# 1_top.net
KiCad netlist of a schematic drawn in Altium Designer
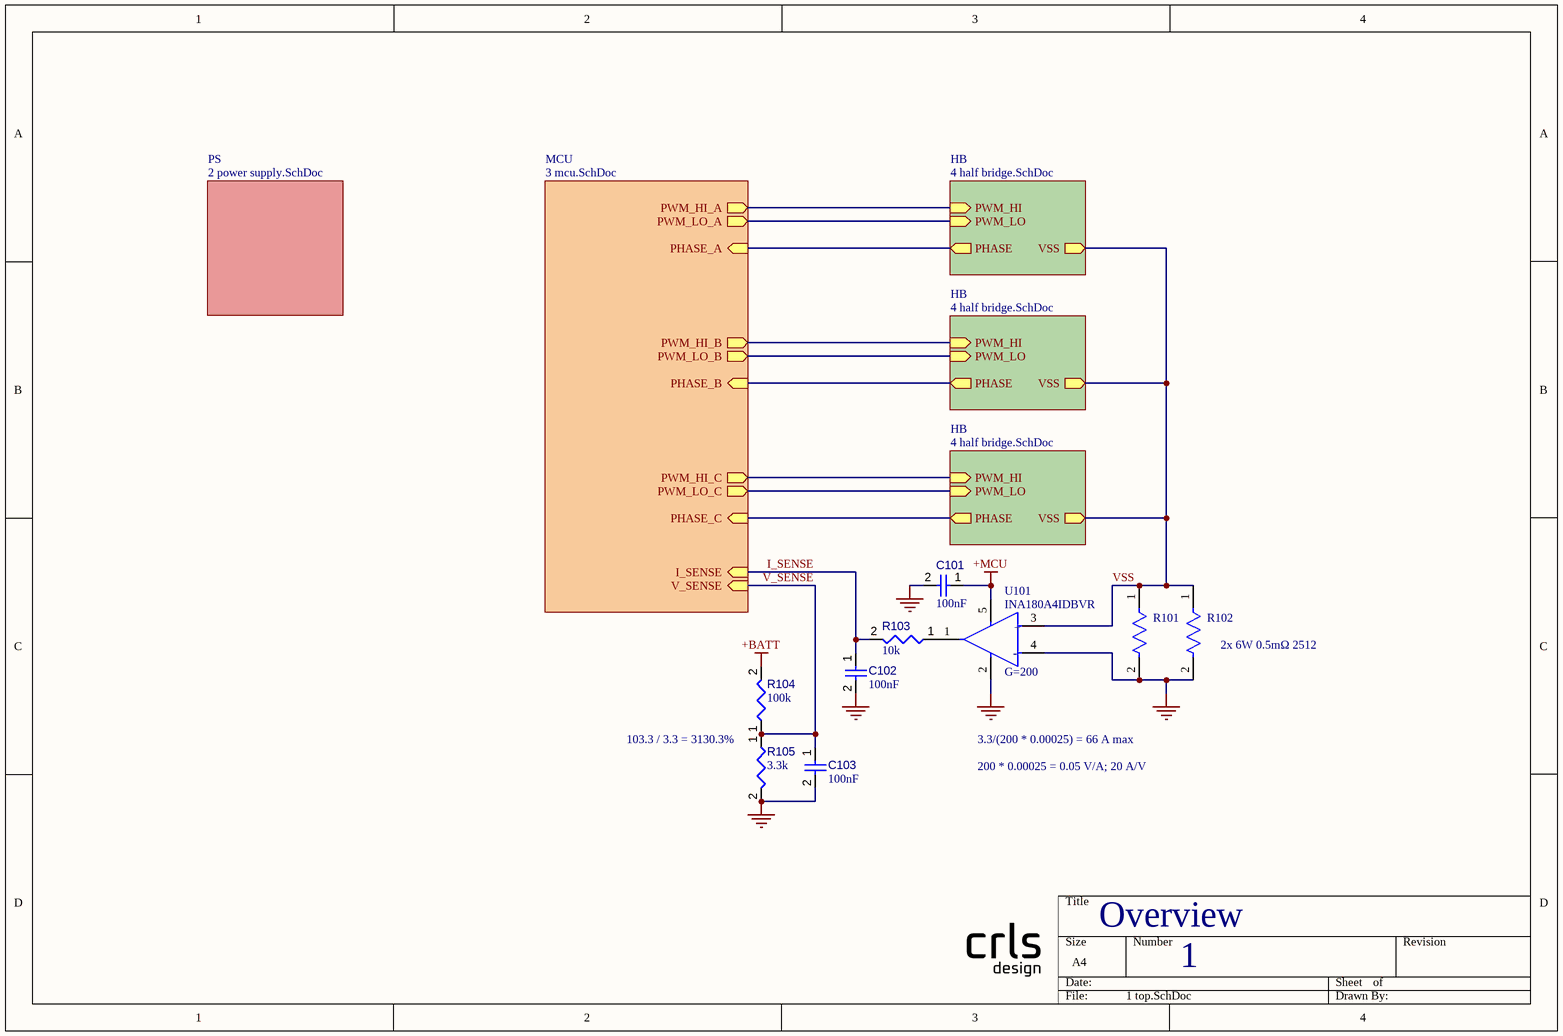
[diagram p0: 1 top.SchDoc]

(export (version "E")
  (design (tool "Eeschema 10.0.6"))
  (components
    (comp (ref "C101")
      (value "100nF")
      (footprint "CAPC0402(1005)60_L")
      (description "Chip Capacitor, 100nF +/-20%, 25V, 0402, Thickness 0.6 mm")
      (fields (field (name "TOLERANCE") "10%") (field (name "Comment") "Capacitor 100nF +/-20% 25V 0402"))
      (libsource (lib "UBC Uncrewed Aircraft Systems") (part "CAP-NP-2"))
    )
    (comp (ref "C102")
      (value "100nF")
      (footprint "CAPC0402(1005)60_L")
      (description "Chip Capacitor, 100nF +/-20%, 25V, 0402, Thickness 0.6 mm")
      (fields (field (name "TOLERANCE") "10%") (field (name "Comment") "Capacitor 100nF +/-20% 25V 0402"))
      (libsource (lib "UBC Uncrewed Aircraft Systems") (part "CAP-NP-2"))
    )
    (comp (ref "C103")
      (value "100nF")
      (footprint "CAPC0402(1005)60_L")
      (description "Chip Capacitor, 100nF +/-20%, 25V, 0402, Thickness 0.6 mm")
      (fields (field (name "TOLERANCE") "10%") (field (name "Comment") "Capacitor 100nF +/-20% 25V 0402"))
      (libsource (lib "UBC Uncrewed Aircraft Systems") (part "CAP-NP-2"))
    )
    (comp (ref "R101")
      (value "PSL2NTEBL500F")
      (footprint "FP-PSL2NTEBL500F-MFG")
      (description "RES 500 UOHM 1% 8W NONSTANDARD")
      (libsource (lib "Altium Content Vault") (part "1029c3af85768c4190bb7ad29bc67b5"))
    )
    (comp (ref "R102")
      (value "PSL2NTEBL500F")
      (footprint "FP-PSL2NTEBL500F-MFG")
      (description "RES 500 UOHM 1% 8W NONSTANDARD")
      (libsource (lib "Altium Content Vault") (part "1029c3af85768c4190bb7ad29bc67b5"))
    )
    (comp (ref "R103")
      (value "10k")
      (footprint "RESC0402(1005)_L")
      (description "Chip Resistor, 10 kOhms, +/-1 %, 63 mW, -55 to 125 degC, 0402")
      (fields (field (name "POWER") "63mW") (field (name "TOLERANCE") "1%"))
      (libsource (lib "UBC Uncrewed Aircraft Systems") (part "RES-2"))
    )
    (comp (ref "R104")
      (value "100k")
      (footprint "RESC0402(1005)_L")
      (description "Chip Resistor, 100 kOhms, +/-1 %, 63 mW, -55 to 155 degC, 0402")
      (fields (field (name "TOLERANCE") "1%") (field (name "POWER") "63mW"))
      (libsource (lib "UBC Uncrewed Aircraft Systems") (part "RES-2"))
    )
    (comp (ref "R105")
      (value "3.3k")
      (footprint "RESC0402(1005)_L")
      (description "Chip Resistor, 3.3 kOhms, +/-1 %, 63 mW, -55 to 155 degC, 0402")
      (fields (field (name "TOLERANCE") "1%") (field (name "POWER") "63mW"))
      (libsource (lib "UBC Uncrewed Aircraft Systems") (part "RES-2"))
    )
    (comp (ref "U101")
      (value "INA180A4IDBVR")
      (footprint "FP-DBV0005A-MFG")
      (description "IC CURR SENSE 1 CIRCUIT SOT23-5")
      (libsource (lib "Altium Content Vault") (part "0a55cf1a948ad01a3239aec1b7efad0"))
    )
  )
  (nets
    (net (code "1") (name "+BATT") (class "Default")
      (node (ref "R104") (pin "2") (pinfunction "2_2") (pintype "passive"))
    )
    (net (code "2") (name "+MCU") (class "Default")
      (node (ref "C101") (pin "1") (pinfunction "1_1") (pintype "passive"))
      (node (ref "U101") (pin "5") (pinfunction "VS_5") (pintype "power_in"))
    )
    (net (code "3") (name "/I_SENSE") (class "Default")
      (node (ref "C102") (pin "1") (pinfunction "1_1") (pintype "passive"))
      (node (ref "R103") (pin "2") (pinfunction "2_2") (pintype "passive"))
    )
    (net (code "13") (name "/VSS") (class "Default")
      (node (ref "R101") (pin "1") (pinfunction "1_1") (pintype "passive"))
      (node (ref "R102") (pin "1") (pinfunction "1_1") (pintype "passive"))
      (node (ref "U101") (pin "3") (pinfunction "IN+_3") (pintype "tri_state"))
    )
    (net (code "14") (name "/V_SENSE") (class "Default")
      (node (ref "C103") (pin "1") (pinfunction "1_1") (pintype "passive"))
      (node (ref "R104") (pin "1") (pinfunction "1_1") (pintype "passive"))
      (node (ref "R105") (pin "1") (pinfunction "1_1") (pintype "passive"))
    )
    (net (code "15") (name "GND") (class "Default")
      (node (ref "C101") (pin "2") (pinfunction "2_2") (pintype "passive"))
      (node (ref "C102") (pin "2") (pinfunction "2_2") (pintype "passive"))
      (node (ref "C103") (pin "2") (pinfunction "2_2") (pintype "passive"))
      (node (ref "R101") (pin "2") (pinfunction "2_2") (pintype "passive"))
      (node (ref "R102") (pin "2") (pinfunction "2_2") (pintype "passive"))
      (node (ref "R105") (pin "2") (pinfunction "2_2") (pintype "passive"))
      (node (ref "U101") (pin "2") (pinfunction "GND_2") (pintype "power_in"))
      (node (ref "U101") (pin "4") (pinfunction "IN-_4") (pintype "tri_state"))
    )
    (net (code "16") (name "Net-(U101-OUT)") (class "Default")
      (node (ref "R103") (pin "1") (pinfunction "1_1") (pintype "passive"))
      (node (ref "U101") (pin "1") (pinfunction "OUT_1") (pintype "passive"))
    )
  )
)
